# TFF_1_0.net
KiCad netlist of a schematic drawn in EAGLE
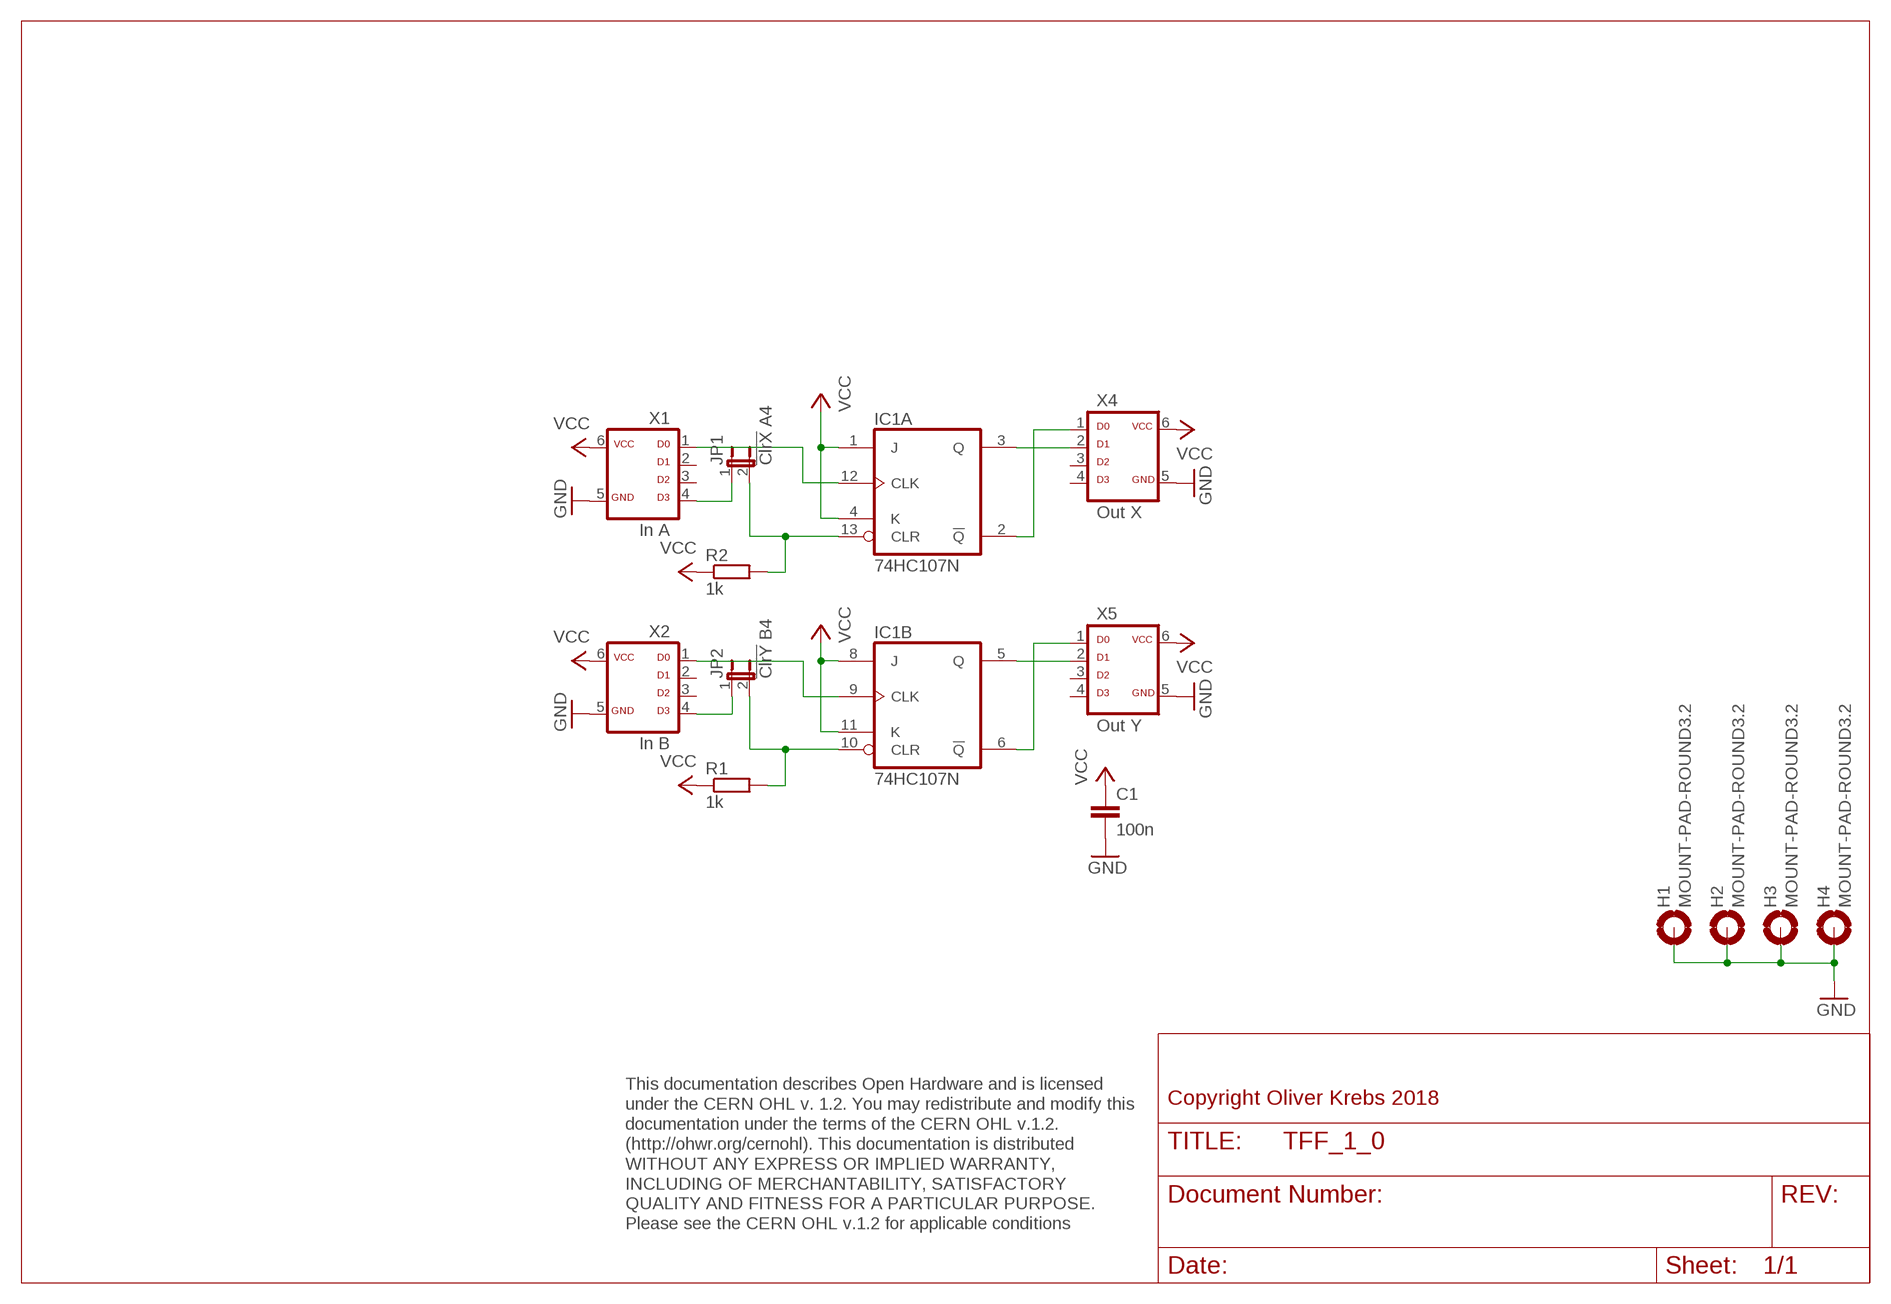
[diagram p0: schematic, sheet 1]

(export (version "E")
  (design (tool "Eeschema 10.0.6"))
  (components
    (comp (ref "C1")
      (value "100n")
      (footprint "eagle-import:C050-025X075")
      (libsource (lib "eagle-import") (part "C-EU050-025X075"))
    )
    (comp (ref "H1")
      (value "MOUNT-PAD-ROUND3.2")
      (footprint "eagle-import:3,2-PAD")
      (libsource (lib "eagle-import") (part "MOUNT-PAD-ROUND3.2"))
    )
    (comp (ref "H2")
      (value "MOUNT-PAD-ROUND3.2")
      (footprint "eagle-import:3,2-PAD")
      (libsource (lib "eagle-import") (part "MOUNT-PAD-ROUND3.2"))
    )
    (comp (ref "H3")
      (value "MOUNT-PAD-ROUND3.2")
      (footprint "eagle-import:3,2-PAD")
      (libsource (lib "eagle-import") (part "MOUNT-PAD-ROUND3.2"))
    )
    (comp (ref "H4")
      (value "MOUNT-PAD-ROUND3.2")
      (footprint "eagle-import:3,2-PAD")
      (libsource (lib "eagle-import") (part "MOUNT-PAD-ROUND3.2"))
    )
    (comp (ref "IC1")
      (value "74HC107N")
      (footprint "eagle-import:DIL14")
      (libsource (lib "eagle-import") (part "74107NHC"))
    )
    (comp (ref "JP1")
      (value "!ClrX! A4")
      (footprint "eagle-import:JP1")
      (libsource (lib "eagle-import") (part "JP1E"))
    )
    (comp (ref "JP2")
      (value "!ClrY! B4")
      (footprint "eagle-import:JP1")
      (libsource (lib "eagle-import") (part "JP1E"))
    )
    (comp (ref "R1")
      (value "1k")
      (footprint "eagle-import:0207_10")
      (libsource (lib "eagle-import") (part "R-EU_0207/10"))
    )
    (comp (ref "R2")
      (value "1k")
      (footprint "eagle-import:0207_10")
      (libsource (lib "eagle-import") (part "R-EU_0207/10"))
    )
    (comp (ref "X1")
      (value "In A")
      (footprint "eagle-import:ML-6")
      (libsource (lib "eagle-import") (part "ML6D"))
    )
    (comp (ref "X2")
      (value "In B")
      (footprint "eagle-import:ML-6")
      (libsource (lib "eagle-import") (part "ML6D"))
    )
    (comp (ref "X4")
      (value "Out X")
      (footprint "eagle-import:ML-6")
      (libsource (lib "eagle-import") (part "ML6D"))
    )
    (comp (ref "X5")
      (value "Out Y")
      (footprint "eagle-import:ML-6")
      (libsource (lib "eagle-import") (part "ML6D"))
    )
  )
  (nets
    (net (code "1") (name "GND") (class "Default")
      (node (ref "C1") (pin "2") (pinfunction "2_2") (pintype "passive"))
      (node (ref "H1") (pin "B3,2") (pinfunction "MOUNT_B3,2") (pintype "passive"))
      (node (ref "H2") (pin "B3,2") (pinfunction "MOUNT_B3,2") (pintype "passive"))
      (node (ref "H3") (pin "B3,2") (pinfunction "MOUNT_B3,2") (pintype "passive"))
      (node (ref "H4") (pin "B3,2") (pinfunction "MOUNT_B3,2") (pintype "passive"))
      (node (ref "X1") (pin "5") (pinfunction "5_5") (pintype "passive"))
      (node (ref "X2") (pin "5") (pinfunction "5_5") (pintype "passive"))
      (node (ref "X4") (pin "5") (pinfunction "5_5") (pintype "passive"))
      (node (ref "X5") (pin "5") (pinfunction "5_5") (pintype "passive"))
    )
    (net (code "2") (name "Net-(IC1A-CLK)") (class "Default")
      (node (ref "IC1") (pin "12") (pinfunction "CLK_12") (pintype "input"))
      (node (ref "X1") (pin "1") (pinfunction "1_1") (pintype "passive"))
    )
    (net (code "3") (name "Net-(IC1A-CLR)") (class "Default")
      (node (ref "IC1") (pin "13") (pinfunction "CLR_13") (pintype "input"))
      (node (ref "JP1") (pin "2") (pinfunction "2_2") (pintype "passive"))
      (node (ref "R2") (pin "2") (pinfunction "2_2") (pintype "passive"))
    )
    (net (code "4") (name "Net-(IC1A-Q)") (class "Default")
      (node (ref "IC1") (pin "3") (pinfunction "Q_3") (pintype "output"))
      (node (ref "X4") (pin "2") (pinfunction "2_2") (pintype "passive"))
    )
    (net (code "5") (name "Net-(IC1A-~{Q})") (class "Default")
      (node (ref "IC1") (pin "2") (pinfunction "~{Q}_2") (pintype "output"))
      (node (ref "X4") (pin "1") (pinfunction "1_1") (pintype "passive"))
    )
    (net (code "6") (name "Net-(IC1B-CLK)") (class "Default")
      (node (ref "IC1") (pin "9") (pinfunction "CLK_9") (pintype "input"))
      (node (ref "X2") (pin "1") (pinfunction "1_1") (pintype "passive"))
    )
    (net (code "7") (name "Net-(IC1B-CLR)") (class "Default")
      (node (ref "IC1") (pin "10") (pinfunction "CLR_10") (pintype "input"))
      (node (ref "JP2") (pin "2") (pinfunction "2_2") (pintype "passive"))
      (node (ref "R1") (pin "2") (pinfunction "2_2") (pintype "passive"))
    )
    (net (code "8") (name "Net-(IC1B-Q)") (class "Default")
      (node (ref "IC1") (pin "5") (pinfunction "Q_5") (pintype "output"))
      (node (ref "X5") (pin "2") (pinfunction "2_2") (pintype "passive"))
    )
    (net (code "9") (name "Net-(IC1B-~{Q})") (class "Default")
      (node (ref "IC1") (pin "6") (pinfunction "~{Q}_6") (pintype "output"))
      (node (ref "X5") (pin "1") (pinfunction "1_1") (pintype "passive"))
    )
    (net (code "10") (name "Net-(JP1-Pad1)") (class "Default")
      (node (ref "JP1") (pin "1") (pinfunction "1_1") (pintype "passive"))
      (node (ref "X1") (pin "4") (pinfunction "4_4") (pintype "passive"))
    )
    (net (code "11") (name "Net-(JP2-Pad1)") (class "Default")
      (node (ref "JP2") (pin "1") (pinfunction "1_1") (pintype "passive"))
      (node (ref "X2") (pin "4") (pinfunction "4_4") (pintype "passive"))
    )
    (net (code "12") (name "VCC") (class "Default")
      (node (ref "C1") (pin "1") (pinfunction "1_1") (pintype "passive"))
      (node (ref "IC1") (pin "1") (pinfunction "J_1") (pintype "input"))
      (node (ref "IC1") (pin "11") (pinfunction "K_11") (pintype "input"))
      (node (ref "IC1") (pin "4") (pinfunction "K_4") (pintype "input"))
      (node (ref "IC1") (pin "8") (pinfunction "J_8") (pintype "input"))
      (node (ref "R1") (pin "1") (pinfunction "1_1") (pintype "passive"))
      (node (ref "R2") (pin "1") (pinfunction "1_1") (pintype "passive"))
      (node (ref "X1") (pin "6") (pinfunction "6_6") (pintype "passive"))
      (node (ref "X2") (pin "6") (pinfunction "6_6") (pintype "passive"))
      (node (ref "X4") (pin "6") (pinfunction "6_6") (pintype "passive"))
      (node (ref "X5") (pin "6") (pinfunction "6_6") (pintype "passive"))
    )
    (net (code "13") (name "unconnected-(X1-Pad2)") (class "Default")
      (node (ref "X1") (pin "2") (pinfunction "2_2") (pintype "passive"))
    )
    (net (code "14") (name "unconnected-(X1-Pad3)") (class "Default")
      (node (ref "X1") (pin "3") (pinfunction "3_3") (pintype "passive"))
    )
    (net (code "15") (name "unconnected-(X2-Pad2)") (class "Default")
      (node (ref "X2") (pin "2") (pinfunction "2_2") (pintype "passive"))
    )
    (net (code "16") (name "unconnected-(X2-Pad3)") (class "Default")
      (node (ref "X2") (pin "3") (pinfunction "3_3") (pintype "passive"))
    )
    (net (code "17") (name "unconnected-(X4-Pad3)") (class "Default")
      (node (ref "X4") (pin "3") (pinfunction "3_3") (pintype "passive"))
    )
    (net (code "18") (name "unconnected-(X4-Pad4)") (class "Default")
      (node (ref "X4") (pin "4") (pinfunction "4_4") (pintype "passive"))
    )
    (net (code "19") (name "unconnected-(X5-Pad3)") (class "Default")
      (node (ref "X5") (pin "3") (pinfunction "3_3") (pintype "passive"))
    )
    (net (code "20") (name "unconnected-(X5-Pad4)") (class "Default")
      (node (ref "X5") (pin "4") (pinfunction "4_4") (pintype "passive"))
    )
  )
)
